# schema.net
KiCad netlist of a schematic drawn in Altium Designer
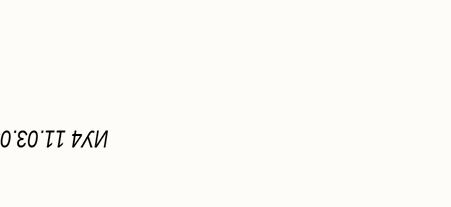
[diagram p0: schema.SchDoc, top left]
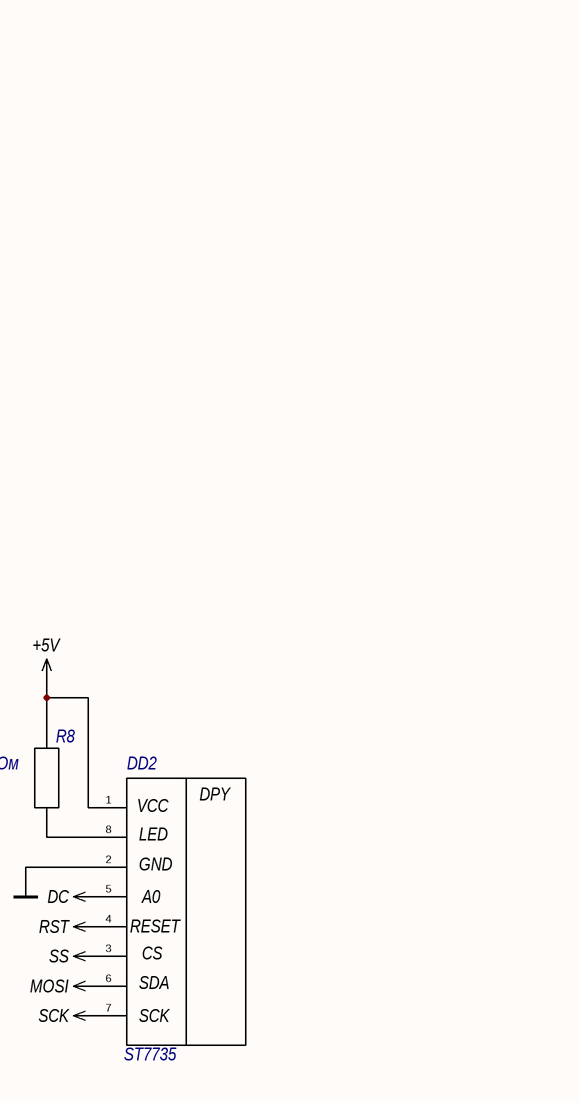
[diagram p1: schema.SchDoc, top right]
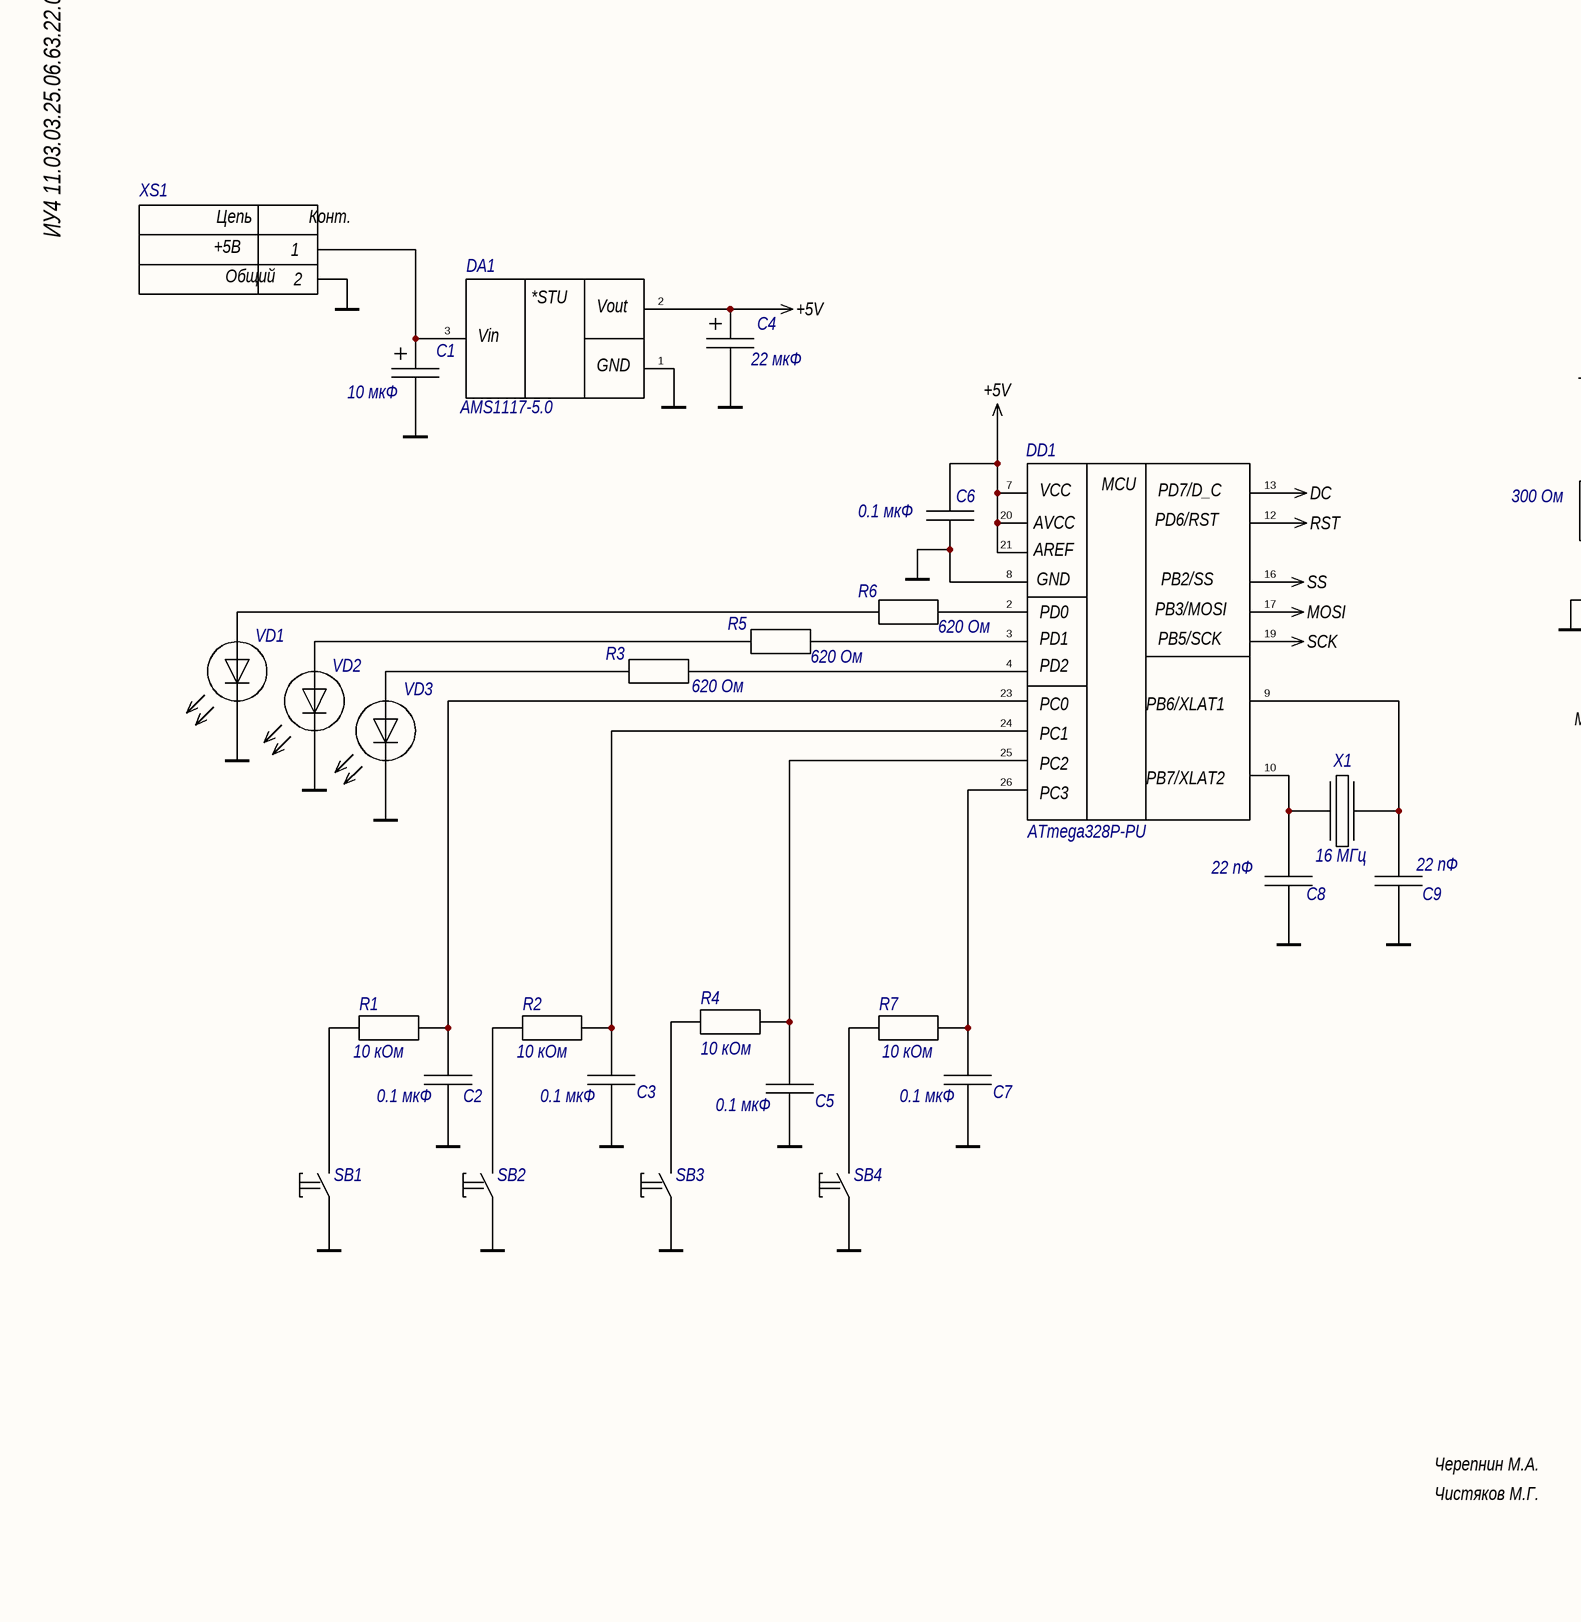
[diagram p2: schema.SchDoc, bottom left]
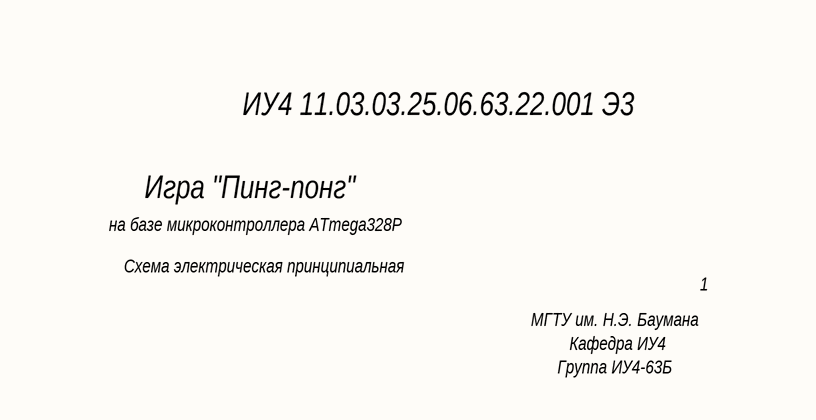
[diagram p3: schema.SchDoc, bottom right]

(export (version "E")
  (design (tool "Eeschema 10.0.6"))
  (components
    (comp (ref "C1") (value "10 мкФ") (footprint "CE") (libsource (lib "components") (part "CE")))
    (comp (ref "C2") (value "0.1 мкФ") (footprint "СC") (libsource (lib "components") (part "C")))
    (comp (ref "C3") (value "0.1 мкФ") (footprint "СC") (libsource (lib "components") (part "C")))
    (comp (ref "C4") (value "22 мкФ") (footprint "CE") (libsource (lib "components") (part "CE")))
    (comp (ref "C5") (value "0.1 мкФ") (footprint "СC") (libsource (lib "components") (part "C")))
    (comp (ref "C6") (value "0.1 мкФ") (footprint "СC") (libsource (lib "components") (part "C")))
    (comp (ref "C7") (value "0.1 мкФ") (footprint "СC") (libsource (lib "components") (part "C")))
    (comp (ref "C8") (value "22 пФ") (footprint "СC") (libsource (lib "components") (part "C")))
    (comp (ref "C9") (value "22 пФ") (footprint "СC") (libsource (lib "components") (part "C")))
    (comp (ref "DA1")
      (value "AMS1117-5.0")
      (footprint "SOT223")
      (libsource (lib "components") (part "Stabilizator"))
    )
    (comp (ref "DD1")
      (value "ATmega328P-PU")
      (footprint "ATMEGA328P-PU")
      (libsource (lib "components") (part "ATmega328P-PU"))
    )
    (comp (ref "DD2") (value "ST7735") (footprint "LCD") (libsource (lib "components") (part "LCD")))
    (comp (ref "R1") (value "10 кОм") (footprint "R") (libsource (lib "components") (part "Resistor")))
    (comp (ref "R2") (value "10 кОм") (footprint "R") (libsource (lib "components") (part "Resistor")))
    (comp (ref "R3") (value "620 Ом") (footprint "R") (libsource (lib "components") (part "Resistor")))
    (comp (ref "R4") (value "10 кОм") (footprint "R") (libsource (lib "components") (part "Resistor")))
    (comp (ref "R5") (value "620 Ом") (footprint "R") (libsource (lib "components") (part "Resistor")))
    (comp (ref "R6") (value "620 Ом") (footprint "R") (libsource (lib "components") (part "Resistor")))
    (comp (ref "R7") (value "10 кОм") (footprint "R") (libsource (lib "components") (part "Resistor")))
    (comp (ref "R8") (value "300 Ом") (footprint "R") (libsource (lib "") (part "Resistor_1")))
    (comp (ref "SB1") (value "Button") (footprint "Button") (libsource (lib "components") (part "Button")))
    (comp (ref "SB2") (value "Button") (footprint "Button") (libsource (lib "components") (part "Button")))
    (comp (ref "SB3") (value "Button") (footprint "Button") (libsource (lib "components") (part "Button")))
    (comp (ref "SB4") (value "Button") (footprint "Button") (libsource (lib "components") (part "Button")))
    (comp (ref "VD1")
      (value "Led")
      (footprint "LED")
      (description "RED")
      (libsource (lib "components") (part "Led"))
    )
    (comp (ref "VD2")
      (value "Led")
      (footprint "LED")
      (description "RED")
      (libsource (lib "components") (part "Led"))
    )
    (comp (ref "VD3")
      (value "Led")
      (footprint "LED")
      (description "RED")
      (libsource (lib "components") (part "Led"))
    )
    (comp (ref "X1") (value "16 МГц") (footprint "Quartz") (libsource (lib "components") (part "Quartz")))
    (comp (ref "XS1") (value "USB") (footprint "TypeC") (libsource (lib "components") (part "USB")))
  )
  (nets
    (net (code "1") (name "+5V") (class "Default")
      (node (ref "C4") (pin "1") (pinfunction "1_1") (pintype "passive"))
      (node (ref "C6") (pin "2") (pinfunction "2_2") (pintype "passive"))
      (node (ref "DA1") (pin "2") (pinfunction "2_2") (pintype "passive"))
      (node (ref "DD1") (pin "20") (pinfunction "20_20") (pintype "passive"))
      (node (ref "DD1") (pin "21") (pinfunction "21_21") (pintype "passive"))
      (node (ref "DD1") (pin "7") (pinfunction "7_7") (pintype "passive"))
      (node (ref "DD2") (pin "1") (pinfunction "1_1") (pintype "passive"))
      (node (ref "R8") (pin "2") (pinfunction "2_2") (pintype "passive"))
    )
    (net (code "2") (name "DC") (class "Default")
      (node (ref "DD1") (pin "13") (pinfunction "13_13") (pintype "passive"))
      (node (ref "DD2") (pin "5") (pinfunction "5_5") (pintype "passive"))
    )
    (net (code "3") (name "GND") (class "Default")
      (node (ref "C1") (pin "2") (pinfunction "2_2") (pintype "passive"))
      (node (ref "C2") (pin "1") (pinfunction "1_1") (pintype "passive"))
      (node (ref "C3") (pin "1") (pinfunction "1_1") (pintype "passive"))
      (node (ref "C4") (pin "2") (pinfunction "2_2") (pintype "passive"))
      (node (ref "C5") (pin "1") (pinfunction "1_1") (pintype "passive"))
      (node (ref "C6") (pin "1") (pinfunction "1_1") (pintype "passive"))
      (node (ref "C7") (pin "1") (pinfunction "1_1") (pintype "passive"))
      (node (ref "C8") (pin "1") (pinfunction "1_1") (pintype "passive"))
      (node (ref "C9") (pin "1") (pinfunction "1_1") (pintype "passive"))
      (node (ref "DA1") (pin "1") (pinfunction "1_1") (pintype "passive"))
      (node (ref "DD1") (pin "8") (pinfunction "8_8") (pintype "passive"))
      (node (ref "DD2") (pin "2") (pinfunction "2_2") (pintype "passive"))
      (node (ref "SB1") (pin "1") (pinfunction "1_1") (pintype "passive"))
      (node (ref "SB2") (pin "1") (pinfunction "1_1") (pintype "passive"))
      (node (ref "SB3") (pin "1") (pinfunction "1_1") (pintype "passive"))
      (node (ref "SB4") (pin "1") (pinfunction "1_1") (pintype "passive"))
      (node (ref "VD1") (pin "1") (pinfunction "1_1") (pintype "passive"))
      (node (ref "VD2") (pin "1") (pinfunction "1_1") (pintype "passive"))
      (node (ref "VD3") (pin "1") (pinfunction "1_1") (pintype "passive"))
      (node (ref "XS1") (pin "GND") (pinfunction "GND_GND") (pintype "passive"))
    )
    (net (code "4") (name "MOSI") (class "Default")
      (node (ref "DD1") (pin "17") (pinfunction "17_17") (pintype "passive"))
      (node (ref "DD2") (pin "6") (pinfunction "6_6") (pintype "passive"))
    )
    (net (code "5") (name "Net-(C1-Pad1)") (class "Default")
      (node (ref "C1") (pin "1") (pinfunction "1_1") (pintype "passive"))
      (node (ref "DA1") (pin "3") (pinfunction "3_3") (pintype "passive"))
      (node (ref "XS1") (pin "VCC") (pinfunction "VCC_VCC") (pintype "passive"))
    )
    (net (code "6") (name "Net-(C2-Pad2)") (class "Default")
      (node (ref "C2") (pin "2") (pinfunction "2_2") (pintype "passive"))
      (node (ref "DD1") (pin "23") (pinfunction "23_23") (pintype "passive"))
      (node (ref "R1") (pin "2") (pinfunction "2_2") (pintype "passive"))
    )
    (net (code "7") (name "Net-(C3-Pad2)") (class "Default")
      (node (ref "C3") (pin "2") (pinfunction "2_2") (pintype "passive"))
      (node (ref "DD1") (pin "24") (pinfunction "24_24") (pintype "passive"))
      (node (ref "R2") (pin "2") (pinfunction "2_2") (pintype "passive"))
    )
    (net (code "8") (name "Net-(C5-Pad2)") (class "Default")
      (node (ref "C5") (pin "2") (pinfunction "2_2") (pintype "passive"))
      (node (ref "DD1") (pin "25") (pinfunction "25_25") (pintype "passive"))
      (node (ref "R4") (pin "2") (pinfunction "2_2") (pintype "passive"))
    )
    (net (code "9") (name "Net-(C7-Pad2)") (class "Default")
      (node (ref "C7") (pin "2") (pinfunction "2_2") (pintype "passive"))
      (node (ref "DD1") (pin "26") (pinfunction "26_26") (pintype "passive"))
      (node (ref "R7") (pin "2") (pinfunction "2_2") (pintype "passive"))
    )
    (net (code "10") (name "Net-(C8-Pad2)") (class "Default")
      (node (ref "C8") (pin "2") (pinfunction "2_2") (pintype "passive"))
      (node (ref "DD1") (pin "10") (pinfunction "10_10") (pintype "passive"))
      (node (ref "X1") (pin "1") (pinfunction "1_1") (pintype "passive"))
    )
    (net (code "11") (name "Net-(C9-Pad2)") (class "Default")
      (node (ref "C9") (pin "2") (pinfunction "2_2") (pintype "passive"))
      (node (ref "DD1") (pin "9") (pinfunction "9_9") (pintype "passive"))
      (node (ref "X1") (pin "2") (pinfunction "2_2") (pintype "passive"))
    )
    (net (code "12") (name "Net-(DD1-Pad2)") (class "Default")
      (node (ref "DD1") (pin "2") (pinfunction "2_2") (pintype "passive"))
      (node (ref "R6") (pin "2") (pinfunction "2_2") (pintype "passive"))
    )
    (net (code "13") (name "Net-(DD1-Pad3)") (class "Default")
      (node (ref "DD1") (pin "3") (pinfunction "3_3") (pintype "passive"))
      (node (ref "R5") (pin "2") (pinfunction "2_2") (pintype "passive"))
    )
    (net (code "14") (name "Net-(DD1-Pad4)") (class "Default")
      (node (ref "DD1") (pin "4") (pinfunction "4_4") (pintype "passive"))
      (node (ref "R3") (pin "2") (pinfunction "2_2") (pintype "passive"))
    )
    (net (code "15") (name "Net-(DD2-Pad8)") (class "Default")
      (node (ref "DD2") (pin "8") (pinfunction "8_8") (pintype "passive"))
      (node (ref "R8") (pin "1") (pinfunction "1_1") (pintype "passive"))
    )
    (net (code "16") (name "Net-(R1-Pad1)") (class "Default")
      (node (ref "R1") (pin "1") (pinfunction "1_1") (pintype "passive"))
      (node (ref "SB1") (pin "2") (pinfunction "2_2") (pintype "passive"))
    )
    (net (code "17") (name "Net-(R2-Pad1)") (class "Default")
      (node (ref "R2") (pin "1") (pinfunction "1_1") (pintype "passive"))
      (node (ref "SB2") (pin "2") (pinfunction "2_2") (pintype "passive"))
    )
    (net (code "18") (name "Net-(R3-Pad1)") (class "Default")
      (node (ref "R3") (pin "1") (pinfunction "1_1") (pintype "passive"))
      (node (ref "VD3") (pin "2") (pinfunction "2_2") (pintype "passive"))
    )
    (net (code "19") (name "Net-(R4-Pad1)") (class "Default")
      (node (ref "R4") (pin "1") (pinfunction "1_1") (pintype "passive"))
      (node (ref "SB3") (pin "2") (pinfunction "2_2") (pintype "passive"))
    )
    (net (code "20") (name "Net-(R5-Pad1)") (class "Default")
      (node (ref "R5") (pin "1") (pinfunction "1_1") (pintype "passive"))
      (node (ref "VD2") (pin "2") (pinfunction "2_2") (pintype "passive"))
    )
    (net (code "21") (name "Net-(R6-Pad1)") (class "Default")
      (node (ref "R6") (pin "1") (pinfunction "1_1") (pintype "passive"))
      (node (ref "VD1") (pin "2") (pinfunction "2_2") (pintype "passive"))
    )
    (net (code "22") (name "Net-(R7-Pad1)") (class "Default")
      (node (ref "R7") (pin "1") (pinfunction "1_1") (pintype "passive"))
      (node (ref "SB4") (pin "2") (pinfunction "2_2") (pintype "passive"))
    )
    (net (code "23") (name "RST") (class "Default")
      (node (ref "DD1") (pin "12") (pinfunction "12_12") (pintype "passive"))
      (node (ref "DD2") (pin "4") (pinfunction "4_4") (pintype "passive"))
    )
    (net (code "24") (name "SCK") (class "Default")
      (node (ref "DD1") (pin "19") (pinfunction "19_19") (pintype "passive"))
      (node (ref "DD2") (pin "7") (pinfunction "7_7") (pintype "passive"))
    )
    (net (code "25") (name "SS") (class "Default")
      (node (ref "DD1") (pin "16") (pinfunction "16_16") (pintype "passive"))
      (node (ref "DD2") (pin "3") (pinfunction "3_3") (pintype "passive"))
    )
  )
)
